# R-Split_level_Shifuter.net
KiCad netlist of a schematic drawn in EAGLE
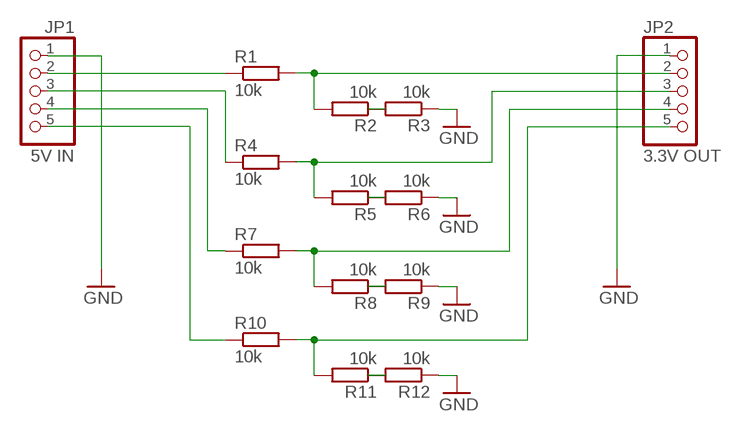
[diagram p0: schematic, sheet 1]

(export (version "E")
  (design (tool "Eeschema 10.0.6"))
  (components
    (comp (ref "JP1")
      (value "5V IN")
      (footprint "eagle-import:1X05")
      (libsource (lib "eagle-import") (part "PINHD-1X5"))
    )
    (comp (ref "JP2")
      (value "3.3V OUT")
      (footprint "eagle-import:1X05")
      (libsource (lib "eagle-import") (part "PINHD-1X5"))
    )
    (comp (ref "R1")
      (value "10k")
      (footprint "eagle-import:0207_7")
      (libsource (lib "eagle-import") (part "R-EU_0207/7"))
    )
    (comp (ref "R2")
      (value "10k")
      (footprint "eagle-import:0207_7")
      (libsource (lib "eagle-import") (part "R-EU_0207/7"))
    )
    (comp (ref "R3")
      (value "10k")
      (footprint "eagle-import:0207_7")
      (libsource (lib "eagle-import") (part "R-EU_0207/7"))
    )
    (comp (ref "R4")
      (value "10k")
      (footprint "eagle-import:0207_7")
      (libsource (lib "eagle-import") (part "R-EU_0207/7"))
    )
    (comp (ref "R5")
      (value "10k")
      (footprint "eagle-import:0207_7")
      (libsource (lib "eagle-import") (part "R-EU_0207/7"))
    )
    (comp (ref "R6")
      (value "10k")
      (footprint "eagle-import:0207_7")
      (libsource (lib "eagle-import") (part "R-EU_0207/7"))
    )
    (comp (ref "R7")
      (value "10k")
      (footprint "eagle-import:0207_7")
      (libsource (lib "eagle-import") (part "R-EU_0207/7"))
    )
    (comp (ref "R8")
      (value "10k")
      (footprint "eagle-import:0207_7")
      (libsource (lib "eagle-import") (part "R-EU_0207/7"))
    )
    (comp (ref "R9")
      (value "10k")
      (footprint "eagle-import:0207_7")
      (libsource (lib "eagle-import") (part "R-EU_0207/7"))
    )
    (comp (ref "R10")
      (value "10k")
      (footprint "eagle-import:0207_7")
      (libsource (lib "eagle-import") (part "R-EU_0207/7"))
    )
    (comp (ref "R11")
      (value "10k")
      (footprint "eagle-import:0207_7")
      (libsource (lib "eagle-import") (part "R-EU_0207/7"))
    )
    (comp (ref "R12")
      (value "10k")
      (footprint "eagle-import:0207_7")
      (libsource (lib "eagle-import") (part "R-EU_0207/7"))
    )
  )
  (nets
    (net (code "1") (name "GND") (class "Default")
      (node (ref "JP1") (pin "1") (pinfunction "1_1") (pintype "passive"))
      (node (ref "JP2") (pin "1") (pinfunction "1_1") (pintype "passive"))
      (node (ref "R12") (pin "1") (pinfunction "1_1") (pintype "passive"))
      (node (ref "R3") (pin "1") (pinfunction "1_1") (pintype "passive"))
      (node (ref "R6") (pin "1") (pinfunction "1_1") (pintype "passive"))
      (node (ref "R9") (pin "1") (pinfunction "1_1") (pintype "passive"))
    )
    (net (code "2") (name "Net-(JP1-Pad2)") (class "Default")
      (node (ref "JP1") (pin "2") (pinfunction "2_2") (pintype "passive"))
      (node (ref "R1") (pin "1") (pinfunction "1_1") (pintype "passive"))
    )
    (net (code "3") (name "Net-(JP1-Pad3)") (class "Default")
      (node (ref "JP1") (pin "3") (pinfunction "3_3") (pintype "passive"))
      (node (ref "R4") (pin "1") (pinfunction "1_1") (pintype "passive"))
    )
    (net (code "4") (name "Net-(JP1-Pad4)") (class "Default")
      (node (ref "JP1") (pin "4") (pinfunction "4_4") (pintype "passive"))
      (node (ref "R7") (pin "1") (pinfunction "1_1") (pintype "passive"))
    )
    (net (code "5") (name "Net-(JP1-Pad5)") (class "Default")
      (node (ref "JP1") (pin "5") (pinfunction "5_5") (pintype "passive"))
      (node (ref "R10") (pin "1") (pinfunction "1_1") (pintype "passive"))
    )
    (net (code "6") (name "Net-(JP2-Pad2)") (class "Default")
      (node (ref "JP2") (pin "2") (pinfunction "2_2") (pintype "passive"))
      (node (ref "R1") (pin "2") (pinfunction "2_2") (pintype "passive"))
      (node (ref "R2") (pin "2") (pinfunction "2_2") (pintype "passive"))
    )
    (net (code "7") (name "Net-(JP2-Pad3)") (class "Default")
      (node (ref "JP2") (pin "3") (pinfunction "3_3") (pintype "passive"))
      (node (ref "R4") (pin "2") (pinfunction "2_2") (pintype "passive"))
      (node (ref "R5") (pin "2") (pinfunction "2_2") (pintype "passive"))
    )
    (net (code "8") (name "Net-(JP2-Pad4)") (class "Default")
      (node (ref "JP2") (pin "4") (pinfunction "4_4") (pintype "passive"))
      (node (ref "R7") (pin "2") (pinfunction "2_2") (pintype "passive"))
      (node (ref "R8") (pin "2") (pinfunction "2_2") (pintype "passive"))
    )
    (net (code "9") (name "Net-(JP2-Pad5)") (class "Default")
      (node (ref "JP2") (pin "5") (pinfunction "5_5") (pintype "passive"))
      (node (ref "R10") (pin "2") (pinfunction "2_2") (pintype "passive"))
      (node (ref "R11") (pin "2") (pinfunction "2_2") (pintype "passive"))
    )
    (net (code "10") (name "Net-(R2-Pad1)") (class "Default")
      (node (ref "R2") (pin "1") (pinfunction "1_1") (pintype "passive"))
      (node (ref "R3") (pin "2") (pinfunction "2_2") (pintype "passive"))
    )
    (net (code "11") (name "Net-(R5-Pad1)") (class "Default")
      (node (ref "R5") (pin "1") (pinfunction "1_1") (pintype "passive"))
      (node (ref "R6") (pin "2") (pinfunction "2_2") (pintype "passive"))
    )
    (net (code "12") (name "Net-(R8-Pad1)") (class "Default")
      (node (ref "R8") (pin "1") (pinfunction "1_1") (pintype "passive"))
      (node (ref "R9") (pin "2") (pinfunction "2_2") (pintype "passive"))
    )
    (net (code "13") (name "Net-(R11-Pad1)") (class "Default")
      (node (ref "R11") (pin "1") (pinfunction "1_1") (pintype "passive"))
      (node (ref "R12") (pin "2") (pinfunction "2_2") (pintype "passive"))
    )
  )
)
